# SPI_Isolator.net
KiCad netlist of a schematic drawn in Altium Designer
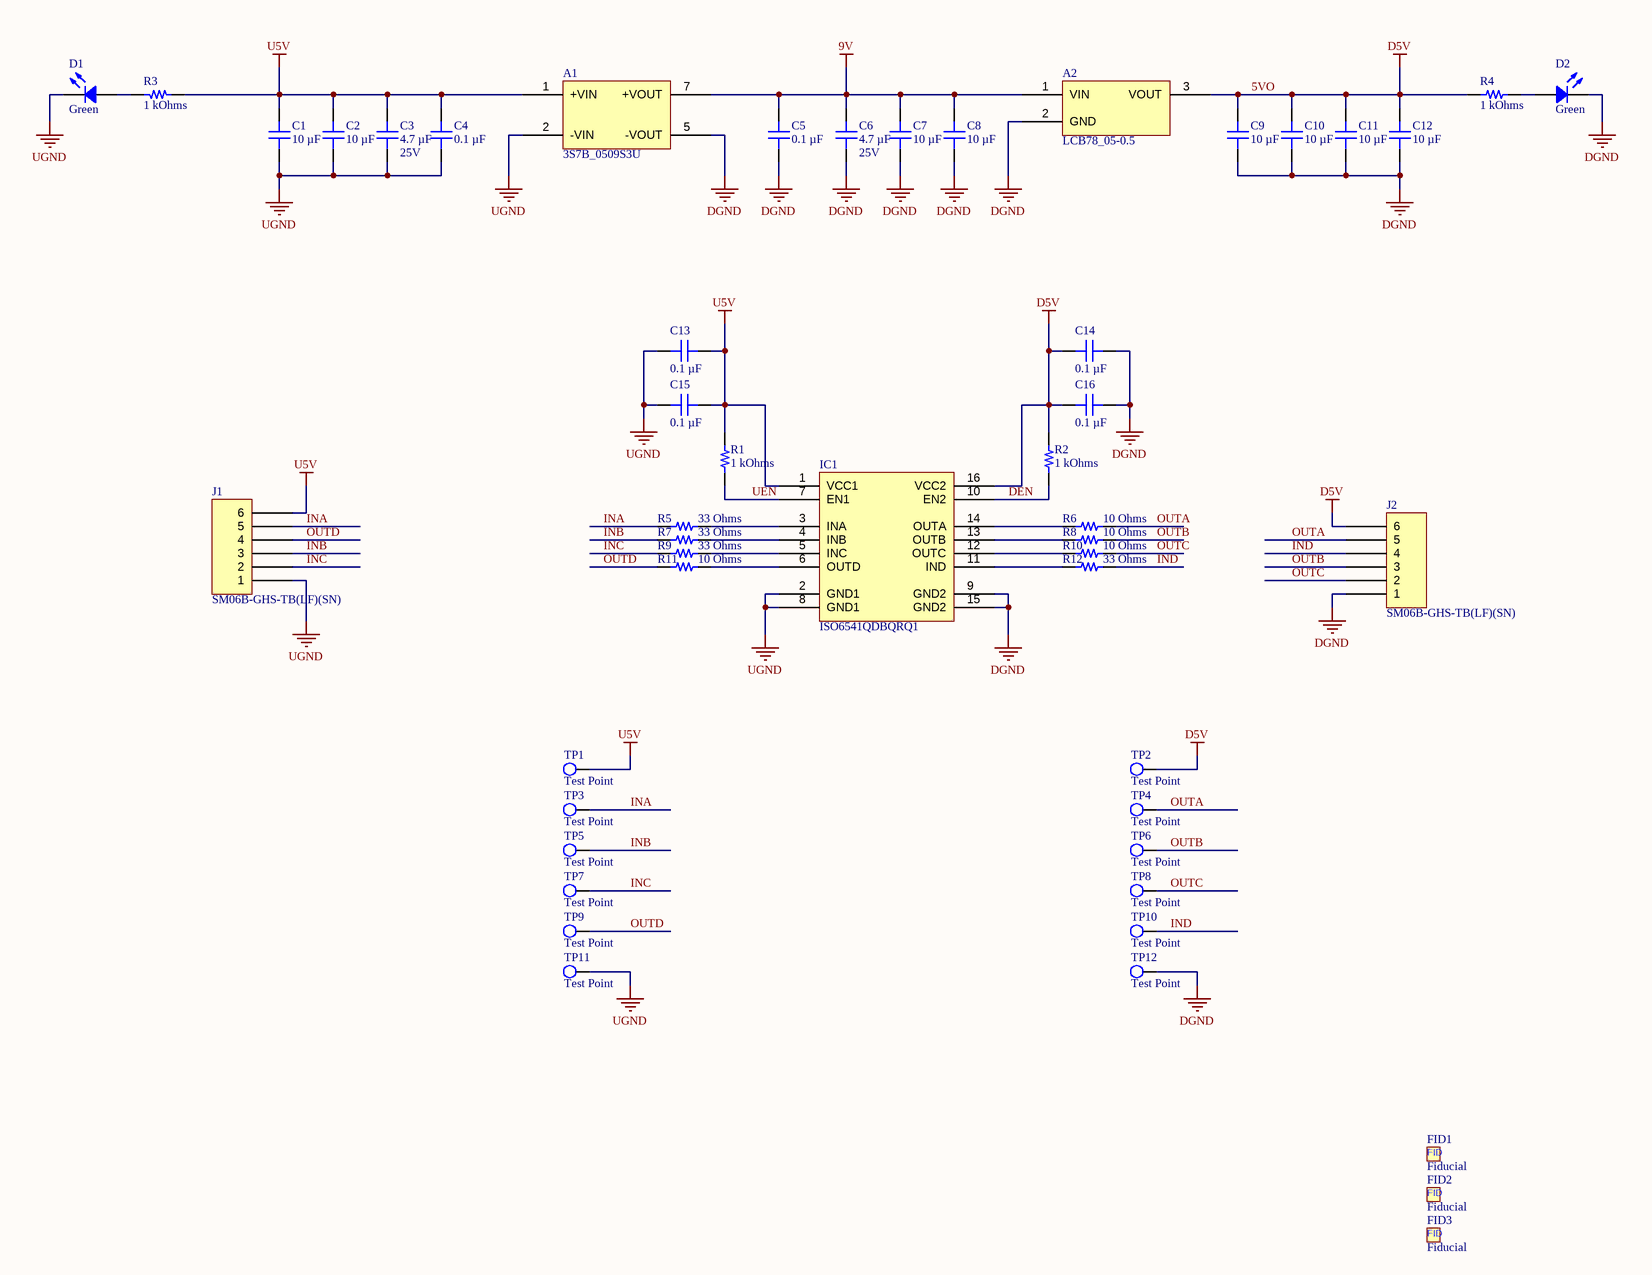
[diagram p0: SPI Isolator.SchDoc]

(export (version "E")
  (design (tool "Eeschema 10.0.6"))
  (components
    (comp (ref "A1")
      (value "3S7B_0509S3U")
      (footprint "GAPTEC 3S7B_3U SINGLE")
      (description "DC-DC")
      (fields (field (name "MANUFACTURER") "GAPTEC Electronic"))
      (libsource (lib "altiumlibrary.com") (part "GAPTEC 3S7B_3U SINGLE"))
    )
    (comp (ref "A2")
      (value "LCB78_05-0.5")
      (footprint "GAPTEC LCB78_0.5")
      (description "DC-DC POL")
      (fields (field (name "MANUFACTURER") "GAPTEC Electronic"))
      (libsource (lib "altiumlibrary.com") (part "GAPTEC LCB78"))
    )
    (comp (ref "C1")
      (value "10 µF")
      (footprint "CAP 1206_3216 - 0.8MM")
      (description "CAP CER 10UF 25V X7R 1206")
      (fields
        (field (name "PART NUMBER") "CL31B106KAHNNNE")
        (field (name "MANUFACTURER") "Samsung Electro-Mechanics")
      )
      (libsource (lib "altiumlibrary.com") (part "Capacitor"))
    )
    (comp (ref "C2")
      (value "10 µF")
      (footprint "CAP 1206_3216 - 0.8MM")
      (description "CAP CER 10UF 25V X7R 1206")
      (fields
        (field (name "PART NUMBER") "CL31B106KAHNNNE")
        (field (name "MANUFACTURER") "Samsung Electro-Mechanics")
      )
      (libsource (lib "altiumlibrary.com") (part "Capacitor"))
    )
    (comp (ref "C3")
      (value "4.7 µF")
      (footprint "MURATA GRM188 0603_1608")
      (description "CAP CER 4.7UF 25V X5R 0603")
      (fields
        (field (name "PART NUMBER") "GRM188R61E475KE11D")
        (field (name "MANUFACTURER") "Murata Electronics")
        (field (name "VOLTAGE - RATED") "25V")
      )
      (libsource (lib "altiumlibrary.com") (part "Capacitor"))
    )
    (comp (ref "C4")
      (value "0.1 µF")
      (footprint "CAP 0603_1608")
      (description "CAP CER 0.1UF 50V X7R 0603")
      (fields
        (field (name "PART NUMBER") "CL10B104KB8NNNC")
        (field (name "MANUFACTURER") "Samsung Electro-Mechanics")
      )
      (libsource (lib "altiumlibrary.com") (part "Capacitor"))
    )
    (comp (ref "C5")
      (value "0.1 µF")
      (footprint "CAP 0603_1608")
      (description "CAP CER 0.1UF 50V X7R 0603")
      (fields
        (field (name "PART NUMBER") "CL10B104KB8NNNC")
        (field (name "MANUFACTURER") "Samsung Electro-Mechanics")
      )
      (libsource (lib "altiumlibrary.com") (part "Capacitor"))
    )
    (comp (ref "C6")
      (value "4.7 µF")
      (footprint "MURATA GRM188 0603_1608")
      (description "CAP CER 4.7UF 25V X5R 0603")
      (fields
        (field (name "PART NUMBER") "GRM188R61E475KE11D")
        (field (name "MANUFACTURER") "Murata Electronics")
        (field (name "VOLTAGE - RATED") "25V")
      )
      (libsource (lib "altiumlibrary.com") (part "Capacitor"))
    )
    (comp (ref "C7")
      (value "10 µF")
      (footprint "CAP 1206_3216 - 0.8MM")
      (description "CAP CER 10UF 25V X7R 1206")
      (fields
        (field (name "PART NUMBER") "CL31B106KAHNNNE")
        (field (name "MANUFACTURER") "Samsung Electro-Mechanics")
      )
      (libsource (lib "altiumlibrary.com") (part "Capacitor"))
    )
    (comp (ref "C8")
      (value "10 µF")
      (footprint "CAP 1206_3216 - 0.8MM")
      (description "CAP CER 10UF 25V X7R 1206")
      (fields
        (field (name "PART NUMBER") "CL31B106KAHNNNE")
        (field (name "MANUFACTURER") "Samsung Electro-Mechanics")
      )
      (libsource (lib "altiumlibrary.com") (part "Capacitor"))
    )
    (comp (ref "C9")
      (value "10 µF")
      (footprint "CAP 1206_3216 - 0.8MM")
      (description "CAP CER 10UF 25V X7R 1206")
      (fields
        (field (name "PART NUMBER") "CL31B106KAHNNNE")
        (field (name "MANUFACTURER") "Samsung Electro-Mechanics")
      )
      (libsource (lib "altiumlibrary.com") (part "Capacitor"))
    )
    (comp (ref "C10")
      (value "10 µF")
      (footprint "CAP 1206_3216 - 0.8MM")
      (description "CAP CER 10UF 25V X7R 1206")
      (fields
        (field (name "PART NUMBER") "CL31B106KAHNNNE")
        (field (name "MANUFACTURER") "Samsung Electro-Mechanics")
      )
      (libsource (lib "altiumlibrary.com") (part "Capacitor"))
    )
    (comp (ref "C11")
      (value "10 µF")
      (footprint "CAP 1206_3216 - 0.8MM")
      (description "CAP CER 10UF 25V X7R 1206")
      (fields
        (field (name "PART NUMBER") "CL31B106KAHNNNE")
        (field (name "MANUFACTURER") "Samsung Electro-Mechanics")
      )
      (libsource (lib "altiumlibrary.com") (part "Capacitor"))
    )
    (comp (ref "C12")
      (value "10 µF")
      (footprint "CAP 1206_3216 - 0.8MM")
      (description "CAP CER 10UF 25V X7R 1206")
      (fields
        (field (name "PART NUMBER") "CL31B106KAHNNNE")
        (field (name "MANUFACTURER") "Samsung Electro-Mechanics")
      )
      (libsource (lib "altiumlibrary.com") (part "Capacitor"))
    )
    (comp (ref "C13")
      (value "0.1 µF")
      (footprint "CAP 0603_1608")
      (description "CAP CER 0.1UF 50V X7R 0603")
      (fields
        (field (name "PART NUMBER") "CL10B104KB8NNNC")
        (field (name "MANUFACTURER") "Samsung Electro-Mechanics")
      )
      (libsource (lib "altiumlibrary.com") (part "Capacitor"))
    )
    (comp (ref "C14")
      (value "0.1 µF")
      (footprint "CAP 0603_1608")
      (description "CAP CER 0.1UF 50V X7R 0603")
      (fields
        (field (name "PART NUMBER") "CL10B104KB8NNNC")
        (field (name "MANUFACTURER") "Samsung Electro-Mechanics")
      )
      (libsource (lib "altiumlibrary.com") (part "Capacitor"))
    )
    (comp (ref "C15")
      (value "0.1 µF")
      (footprint "CAP 0603_1608")
      (description "CAP CER 0.1UF 50V X7R 0603")
      (fields
        (field (name "PART NUMBER") "CL10B104KB8NNNC")
        (field (name "MANUFACTURER") "Samsung Electro-Mechanics")
      )
      (libsource (lib "altiumlibrary.com") (part "Capacitor"))
    )
    (comp (ref "C16")
      (value "0.1 µF")
      (footprint "CAP 0603_1608")
      (description "CAP CER 0.1UF 50V X7R 0603")
      (fields
        (field (name "PART NUMBER") "CL10B104KB8NNNC")
        (field (name "MANUFACTURER") "Samsung Electro-Mechanics")
      )
      (libsource (lib "altiumlibrary.com") (part "Capacitor"))
    )
    (comp (ref "D1")
      (value "Green")
      (footprint "LED 0603_1608 GREEN")
      (description "LED GREEN CLEAR 0603 SMD")
      (fields
        (field (name "PART NUMBER") "LG Q976.01-MGNI-35-1")
        (field (name "MANUFACTURER") "ams-OSRAM USA Inc.")
      )
      (libsource (lib "altiumlibrary.com") (part "LED"))
    )
    (comp (ref "D2")
      (value "Green")
      (footprint "LED 0603_1608 GREEN")
      (description "LED GREEN CLEAR 0603 SMD")
      (fields
        (field (name "PART NUMBER") "LG Q976.01-MGNI-35-1")
        (field (name "MANUFACTURER") "ams-OSRAM USA Inc.")
      )
      (libsource (lib "altiumlibrary.com") (part "LED"))
    )
    (comp (ref "FID1")
      (value "Fiducial")
      (footprint "Fiducial-1mm")
      (libsource (lib "Original Circuit") (part "Fiducial"))
    )
    (comp (ref "FID2")
      (value "Fiducial")
      (footprint "Fiducial-1mm")
      (libsource (lib "Original Circuit") (part "Fiducial"))
    )
    (comp (ref "FID3")
      (value "Fiducial")
      (footprint "Fiducial-1mm")
      (libsource (lib "Original Circuit") (part "Fiducial"))
    )
    (comp (ref "IC1")
      (value "ISO6541QDBQRQ1")
      (footprint "TI SSOP-16 DBQ0016A")
      (description "AUTOMOTIVE, 100-V ISOLATION")
      (fields (field (name "MANUFACTURER") "Texas Instruments"))
      (libsource (lib "altiumlibrary.com") (part "TI ISO6541-Q1"))
    )
    (comp (ref "J1")
      (value "SM06B-GHS-TB(LF)(SN)")
      (footprint "JST SM06B-GHS-TB")
      (description "CONN HEADER SMD R/A 6POS 1.25MM")
      (fields (field (name "MANUFACTURER") "JST Sales America Inc."))
      (libsource (lib "altiumlibrary.com") (part "6 Pin"))
    )
    (comp (ref "J2")
      (value "SM06B-GHS-TB(LF)(SN)")
      (footprint "JST SM06B-GHS-TB")
      (description "CONN HEADER SMD R/A 6POS 1.25MM")
      (fields (field (name "MANUFACTURER") "JST Sales America Inc."))
      (libsource (lib "") (part "6 Pin_1"))
    )
    (comp (ref "R1")
      (value "1 kOhms")
      (footprint "YAGEO RES 0402_1005")
      (description "RES 1K OHM 1% 1/16W 0402")
      (fields (field (name "PART NUMBER") "RC0402FR-071KP") (field (name "MANUFACTURER") "Yageo"))
      (libsource (lib "altiumlibrary.com") (part "Resistor"))
    )
    (comp (ref "R2")
      (value "1 kOhms")
      (footprint "YAGEO RES 0402_1005")
      (description "RES 1K OHM 1% 1/16W 0402")
      (fields (field (name "PART NUMBER") "RC0402FR-071KP") (field (name "MANUFACTURER") "Yageo"))
      (libsource (lib "altiumlibrary.com") (part "Resistor"))
    )
    (comp (ref "R3")
      (value "1 kOhms")
      (footprint "YAGEO RES 0402_1005")
      (description "RES 1K OHM 1% 1/16W 0402")
      (fields (field (name "PART NUMBER") "RC0402FR-071KP") (field (name "MANUFACTURER") "Yageo"))
      (libsource (lib "altiumlibrary.com") (part "Resistor"))
    )
    (comp (ref "R4")
      (value "1 kOhms")
      (footprint "YAGEO RES 0402_1005")
      (description "RES 1K OHM 1% 1/16W 0402")
      (fields (field (name "PART NUMBER") "RC0402FR-071KP") (field (name "MANUFACTURER") "Yageo"))
      (libsource (lib "altiumlibrary.com") (part "Resistor"))
    )
    (comp (ref "R5")
      (value "33 Ohms")
      (footprint "YAGEO RES 0402_1005")
      (description "RES 33 OHM 1% 1/16W 0402")
      (fields (field (name "PART NUMBER") "RC0402FR-0733RP") (field (name "MANUFACTURER") "Yageo"))
      (libsource (lib "altiumlibrary.com") (part "Resistor"))
    )
    (comp (ref "R6")
      (value "10 Ohms")
      (footprint "YAGEO RES 0402_1005")
      (description "RES 10 OHM 1% 1/16W 0402")
      (fields (field (name "PART NUMBER") "RC0402FR-1310RL") (field (name "MANUFACTURER") "Yageo"))
      (libsource (lib "altiumlibrary.com") (part "Resistor"))
    )
    (comp (ref "R7")
      (value "33 Ohms")
      (footprint "YAGEO RES 0402_1005")
      (description "RES 33 OHM 1% 1/16W 0402")
      (fields (field (name "PART NUMBER") "RC0402FR-0733RP") (field (name "MANUFACTURER") "Yageo"))
      (libsource (lib "altiumlibrary.com") (part "Resistor"))
    )
    (comp (ref "R8")
      (value "10 Ohms")
      (footprint "YAGEO RES 0402_1005")
      (description "RES 10 OHM 1% 1/16W 0402")
      (fields (field (name "PART NUMBER") "RC0402FR-1310RL") (field (name "MANUFACTURER") "Yageo"))
      (libsource (lib "altiumlibrary.com") (part "Resistor"))
    )
    (comp (ref "R9")
      (value "33 Ohms")
      (footprint "YAGEO RES 0402_1005")
      (description "RES 33 OHM 1% 1/16W 0402")
      (fields (field (name "PART NUMBER") "RC0402FR-0733RP") (field (name "MANUFACTURER") "Yageo"))
      (libsource (lib "altiumlibrary.com") (part "Resistor"))
    )
    (comp (ref "R10")
      (value "10 Ohms")
      (footprint "YAGEO RES 0402_1005")
      (description "RES 10 OHM 1% 1/16W 0402")
      (fields (field (name "PART NUMBER") "RC0402FR-1310RL") (field (name "MANUFACTURER") "Yageo"))
      (libsource (lib "altiumlibrary.com") (part "Resistor"))
    )
    (comp (ref "R11")
      (value "10 Ohms")
      (footprint "YAGEO RES 0402_1005")
      (description "RES 10 OHM 1% 1/16W 0402")
      (fields (field (name "PART NUMBER") "RC0402FR-1310RL") (field (name "MANUFACTURER") "Yageo"))
      (libsource (lib "altiumlibrary.com") (part "Resistor"))
    )
    (comp (ref "R12")
      (value "33 Ohms")
      (footprint "YAGEO RES 0402_1005")
      (description "RES 33 OHM 1% 1/16W 0402")
      (fields (field (name "PART NUMBER") "RC0402FR-0733RP") (field (name "MANUFACTURER") "Yageo"))
      (libsource (lib "altiumlibrary.com") (part "Resistor"))
    )
    (comp (ref "TP1")
      (value "Test Point")
      (footprint "TestPoint-1.5mm")
      (libsource (lib "Original Circuit") (part "Test Point"))
    )
    (comp (ref "TP2")
      (value "Test Point")
      (footprint "TestPoint-1.5mm")
      (libsource (lib "Original Circuit") (part "Test Point"))
    )
    (comp (ref "TP3")
      (value "Test Point")
      (footprint "TestPoint-1.5mm")
      (libsource (lib "Original Circuit") (part "Test Point"))
    )
    (comp (ref "TP4")
      (value "Test Point")
      (footprint "TestPoint-1.5mm")
      (libsource (lib "Original Circuit") (part "Test Point"))
    )
    (comp (ref "TP5")
      (value "Test Point")
      (footprint "TestPoint-1.5mm")
      (libsource (lib "Original Circuit") (part "Test Point"))
    )
    (comp (ref "TP6")
      (value "Test Point")
      (footprint "TestPoint-1.5mm")
      (libsource (lib "Original Circuit") (part "Test Point"))
    )
    (comp (ref "TP7")
      (value "Test Point")
      (footprint "TestPoint-1.5mm")
      (libsource (lib "Original Circuit") (part "Test Point"))
    )
    (comp (ref "TP8")
      (value "Test Point")
      (footprint "TestPoint-1.5mm")
      (libsource (lib "Original Circuit") (part "Test Point"))
    )
    (comp (ref "TP9")
      (value "Test Point")
      (footprint "TestPoint-1.5mm")
      (libsource (lib "Original Circuit") (part "Test Point"))
    )
    (comp (ref "TP10")
      (value "Test Point")
      (footprint "TestPoint-1.5mm")
      (libsource (lib "Original Circuit") (part "Test Point"))
    )
    (comp (ref "TP11")
      (value "Test Point")
      (footprint "TestPoint-1.5mm")
      (libsource (lib "Original Circuit") (part "Test Point"))
    )
    (comp (ref "TP12")
      (value "Test Point")
      (footprint "TestPoint-1.5mm")
      (libsource (lib "Original Circuit") (part "Test Point"))
    )
  )
  (nets
    (net (code "1") (name "/DEN") (class "Default")
      (node (ref "IC1") (pin "10") (pinfunction "EN2_10") (pintype "passive"))
      (node (ref "R2") (pin "2") (pinfunction "2_2") (pintype "passive"))
    )
    (net (code "2") (name "/INA") (class "Default")
      (node (ref "J1") (pin "5") (pinfunction "5_5") (pintype "passive"))
      (node (ref "R5") (pin "2") (pinfunction "2_2") (pintype "passive"))
      (node (ref "TP3") (pin "1") (pinfunction "TP_1") (pintype "passive"))
    )
    (net (code "3") (name "/INB") (class "Default")
      (node (ref "J1") (pin "3") (pinfunction "3_3") (pintype "passive"))
      (node (ref "R7") (pin "2") (pinfunction "2_2") (pintype "passive"))
      (node (ref "TP5") (pin "1") (pinfunction "TP_1") (pintype "passive"))
    )
    (net (code "4") (name "/INC") (class "Default")
      (node (ref "J1") (pin "2") (pinfunction "2_2") (pintype "passive"))
      (node (ref "R9") (pin "2") (pinfunction "2_2") (pintype "passive"))
      (node (ref "TP7") (pin "1") (pinfunction "TP_1") (pintype "passive"))
    )
    (net (code "5") (name "/IND") (class "Default")
      (node (ref "J2") (pin "4") (pinfunction "4_4") (pintype "passive"))
      (node (ref "R12") (pin "1") (pinfunction "1_1") (pintype "passive"))
      (node (ref "TP10") (pin "1") (pinfunction "TP_1") (pintype "passive"))
    )
    (net (code "6") (name "/OUTA") (class "Default")
      (node (ref "J2") (pin "5") (pinfunction "5_5") (pintype "passive"))
      (node (ref "R6") (pin "2") (pinfunction "2_2") (pintype "passive"))
      (node (ref "TP4") (pin "1") (pinfunction "TP_1") (pintype "passive"))
    )
    (net (code "7") (name "/OUTB") (class "Default")
      (node (ref "J2") (pin "3") (pinfunction "3_3") (pintype "passive"))
      (node (ref "R8") (pin "2") (pinfunction "2_2") (pintype "passive"))
      (node (ref "TP6") (pin "1") (pinfunction "TP_1") (pintype "passive"))
    )
    (net (code "8") (name "/OUTC") (class "Default")
      (node (ref "J2") (pin "2") (pinfunction "2_2") (pintype "passive"))
      (node (ref "R10") (pin "2") (pinfunction "2_2") (pintype "passive"))
      (node (ref "TP8") (pin "1") (pinfunction "TP_1") (pintype "passive"))
    )
    (net (code "9") (name "/OUTD") (class "Default")
      (node (ref "J1") (pin "4") (pinfunction "4_4") (pintype "passive"))
      (node (ref "R11") (pin "1") (pinfunction "1_1") (pintype "passive"))
      (node (ref "TP9") (pin "1") (pinfunction "TP_1") (pintype "passive"))
    )
    (net (code "10") (name "/UEN") (class "Default")
      (node (ref "IC1") (pin "7") (pinfunction "EN1_7") (pintype "passive"))
      (node (ref "R1") (pin "2") (pinfunction "2_2") (pintype "passive"))
    )
    (net (code "11") (name "9V") (class "Default")
      (node (ref "A1") (pin "7") (pinfunction "+VOUT_7") (pintype "passive"))
      (node (ref "A2") (pin "1") (pinfunction "VIN_1") (pintype "passive"))
      (node (ref "C5") (pin "2") (pinfunction "2_2") (pintype "passive"))
      (node (ref "C6") (pin "2") (pinfunction "2_2") (pintype "passive"))
      (node (ref "C7") (pin "2") (pinfunction "2_2") (pintype "passive"))
      (node (ref "C8") (pin "2") (pinfunction "2_2") (pintype "passive"))
    )
    (net (code "12") (name "D5V") (class "Default")
      (node (ref "A2") (pin "3") (pinfunction "VOUT_3") (pintype "passive"))
      (node (ref "C10") (pin "2") (pinfunction "2_2") (pintype "passive"))
      (node (ref "C11") (pin "2") (pinfunction "2_2") (pintype "passive"))
      (node (ref "C12") (pin "2") (pinfunction "2_2") (pintype "passive"))
      (node (ref "C14") (pin "2") (pinfunction "2_2") (pintype "passive"))
      (node (ref "C16") (pin "2") (pinfunction "2_2") (pintype "passive"))
      (node (ref "C9") (pin "2") (pinfunction "2_2") (pintype "passive"))
      (node (ref "IC1") (pin "16") (pinfunction "VCC2_16") (pintype "passive"))
      (node (ref "J2") (pin "6") (pinfunction "6_6") (pintype "passive"))
      (node (ref "R2") (pin "1") (pinfunction "1_1") (pintype "passive"))
      (node (ref "R4") (pin "1") (pinfunction "1_1") (pintype "passive"))
      (node (ref "TP2") (pin "1") (pinfunction "TP_1") (pintype "passive"))
    )
    (net (code "13") (name "DGND") (class "Default")
      (node (ref "A1") (pin "5") (pinfunction "-VOUT_5") (pintype "passive"))
      (node (ref "A2") (pin "2") (pinfunction "GND_2") (pintype "passive"))
      (node (ref "C10") (pin "1") (pinfunction "1_1") (pintype "passive"))
      (node (ref "C11") (pin "1") (pinfunction "1_1") (pintype "passive"))
      (node (ref "C12") (pin "1") (pinfunction "1_1") (pintype "passive"))
      (node (ref "C14") (pin "1") (pinfunction "1_1") (pintype "passive"))
      (node (ref "C16") (pin "1") (pinfunction "1_1") (pintype "passive"))
      (node (ref "C5") (pin "1") (pinfunction "1_1") (pintype "passive"))
      (node (ref "C6") (pin "1") (pinfunction "1_1") (pintype "passive"))
      (node (ref "C7") (pin "1") (pinfunction "1_1") (pintype "passive"))
      (node (ref "C8") (pin "1") (pinfunction "1_1") (pintype "passive"))
      (node (ref "C9") (pin "1") (pinfunction "1_1") (pintype "passive"))
      (node (ref "D2") (pin "2") (pinfunction "2_2") (pintype "passive"))
      (node (ref "IC1") (pin "15") (pinfunction "GND2_15") (pintype "passive"))
      (node (ref "IC1") (pin "9") (pinfunction "GND2_9") (pintype "passive"))
      (node (ref "J2") (pin "1") (pinfunction "1_1") (pintype "passive"))
      (node (ref "TP12") (pin "1") (pinfunction "TP_1") (pintype "passive"))
    )
    (net (code "14") (name "Net-(D1-Pad1)") (class "Default")
      (node (ref "D1") (pin "1") (pinfunction "1_1") (pintype "passive"))
      (node (ref "R3") (pin "2") (pinfunction "2_2") (pintype "passive"))
    )
    (net (code "15") (name "Net-(D2-Pad1)") (class "Default")
      (node (ref "D2") (pin "1") (pinfunction "1_1") (pintype "passive"))
      (node (ref "R4") (pin "2") (pinfunction "2_2") (pintype "passive"))
    )
    (net (code "16") (name "Net-(IC1-INA)") (class "Default")
      (node (ref "IC1") (pin "3") (pinfunction "INA_3") (pintype "passive"))
      (node (ref "R5") (pin "1") (pinfunction "1_1") (pintype "passive"))
    )
    (net (code "17") (name "Net-(IC1-INB)") (class "Default")
      (node (ref "IC1") (pin "4") (pinfunction "INB_4") (pintype "passive"))
      (node (ref "R7") (pin "1") (pinfunction "1_1") (pintype "passive"))
    )
    (net (code "18") (name "Net-(IC1-INC)") (class "Default")
      (node (ref "IC1") (pin "5") (pinfunction "INC_5") (pintype "passive"))
      (node (ref "R9") (pin "1") (pinfunction "1_1") (pintype "passive"))
    )
    (net (code "19") (name "Net-(IC1-IND)") (class "Default")
      (node (ref "IC1") (pin "11") (pinfunction "IND_11") (pintype "passive"))
      (node (ref "R12") (pin "2") (pinfunction "2_2") (pintype "passive"))
    )
    (net (code "20") (name "Net-(IC1-OUTA)") (class "Default")
      (node (ref "IC1") (pin "14") (pinfunction "OUTA_14") (pintype "passive"))
      (node (ref "R6") (pin "1") (pinfunction "1_1") (pintype "passive"))
    )
    (net (code "21") (name "Net-(IC1-OUTB)") (class "Default")
      (node (ref "IC1") (pin "13") (pinfunction "OUTB_13") (pintype "passive"))
      (node (ref "R8") (pin "1") (pinfunction "1_1") (pintype "passive"))
    )
    (net (code "22") (name "Net-(IC1-OUTC)") (class "Default")
      (node (ref "IC1") (pin "12") (pinfunction "OUTC_12") (pintype "passive"))
      (node (ref "R10") (pin "1") (pinfunction "1_1") (pintype "passive"))
    )
    (net (code "23") (name "Net-(IC1-OUTD)") (class "Default")
      (node (ref "IC1") (pin "6") (pinfunction "OUTD_6") (pintype "passive"))
      (node (ref "R11") (pin "2") (pinfunction "2_2") (pintype "passive"))
    )
    (net (code "24") (name "U5V") (class "Default")
      (node (ref "A1") (pin "1") (pinfunction "+VIN_1") (pintype "passive"))
      (node (ref "C1") (pin "2") (pinfunction "2_2") (pintype "passive"))
      (node (ref "C13") (pin "1") (pinfunction "1_1") (pintype "passive"))
      (node (ref "C15") (pin "1") (pinfunction "1_1") (pintype "passive"))
      (node (ref "C2") (pin "2") (pinfunction "2_2") (pintype "passive"))
      (node (ref "C3") (pin "2") (pinfunction "2_2") (pintype "passive"))
      (node (ref "C4") (pin "2") (pinfunction "2_2") (pintype "passive"))
      (node (ref "IC1") (pin "1") (pinfunction "VCC1_1") (pintype "passive"))
      (node (ref "J1") (pin "6") (pinfunction "6_6") (pintype "passive"))
      (node (ref "R1") (pin "1") (pinfunction "1_1") (pintype "passive"))
      (node (ref "R3") (pin "1") (pinfunction "1_1") (pintype "passive"))
      (node (ref "TP1") (pin "1") (pinfunction "TP_1") (pintype "passive"))
    )
    (net (code "25") (name "UGND") (class "Default")
      (node (ref "A1") (pin "2") (pinfunction "-VIN_2") (pintype "passive"))
      (node (ref "C1") (pin "1") (pinfunction "1_1") (pintype "passive"))
      (node (ref "C13") (pin "2") (pinfunction "2_2") (pintype "passive"))
      (node (ref "C15") (pin "2") (pinfunction "2_2") (pintype "passive"))
      (node (ref "C2") (pin "1") (pinfunction "1_1") (pintype "passive"))
      (node (ref "C3") (pin "1") (pinfunction "1_1") (pintype "passive"))
      (node (ref "C4") (pin "1") (pinfunction "1_1") (pintype "passive"))
      (node (ref "D1") (pin "2") (pinfunction "2_2") (pintype "passive"))
      (node (ref "IC1") (pin "2") (pinfunction "GND1_2") (pintype "passive"))
      (node (ref "IC1") (pin "8") (pinfunction "GND1_8") (pintype "passive"))
      (node (ref "J1") (pin "1") (pinfunction "1_1") (pintype "passive"))
      (node (ref "TP11") (pin "1") (pinfunction "TP_1") (pintype "passive"))
    )
  )
)
